# Keng_Seng_Task_2.net
KiCad netlist of a schematic drawn in Altium Designer
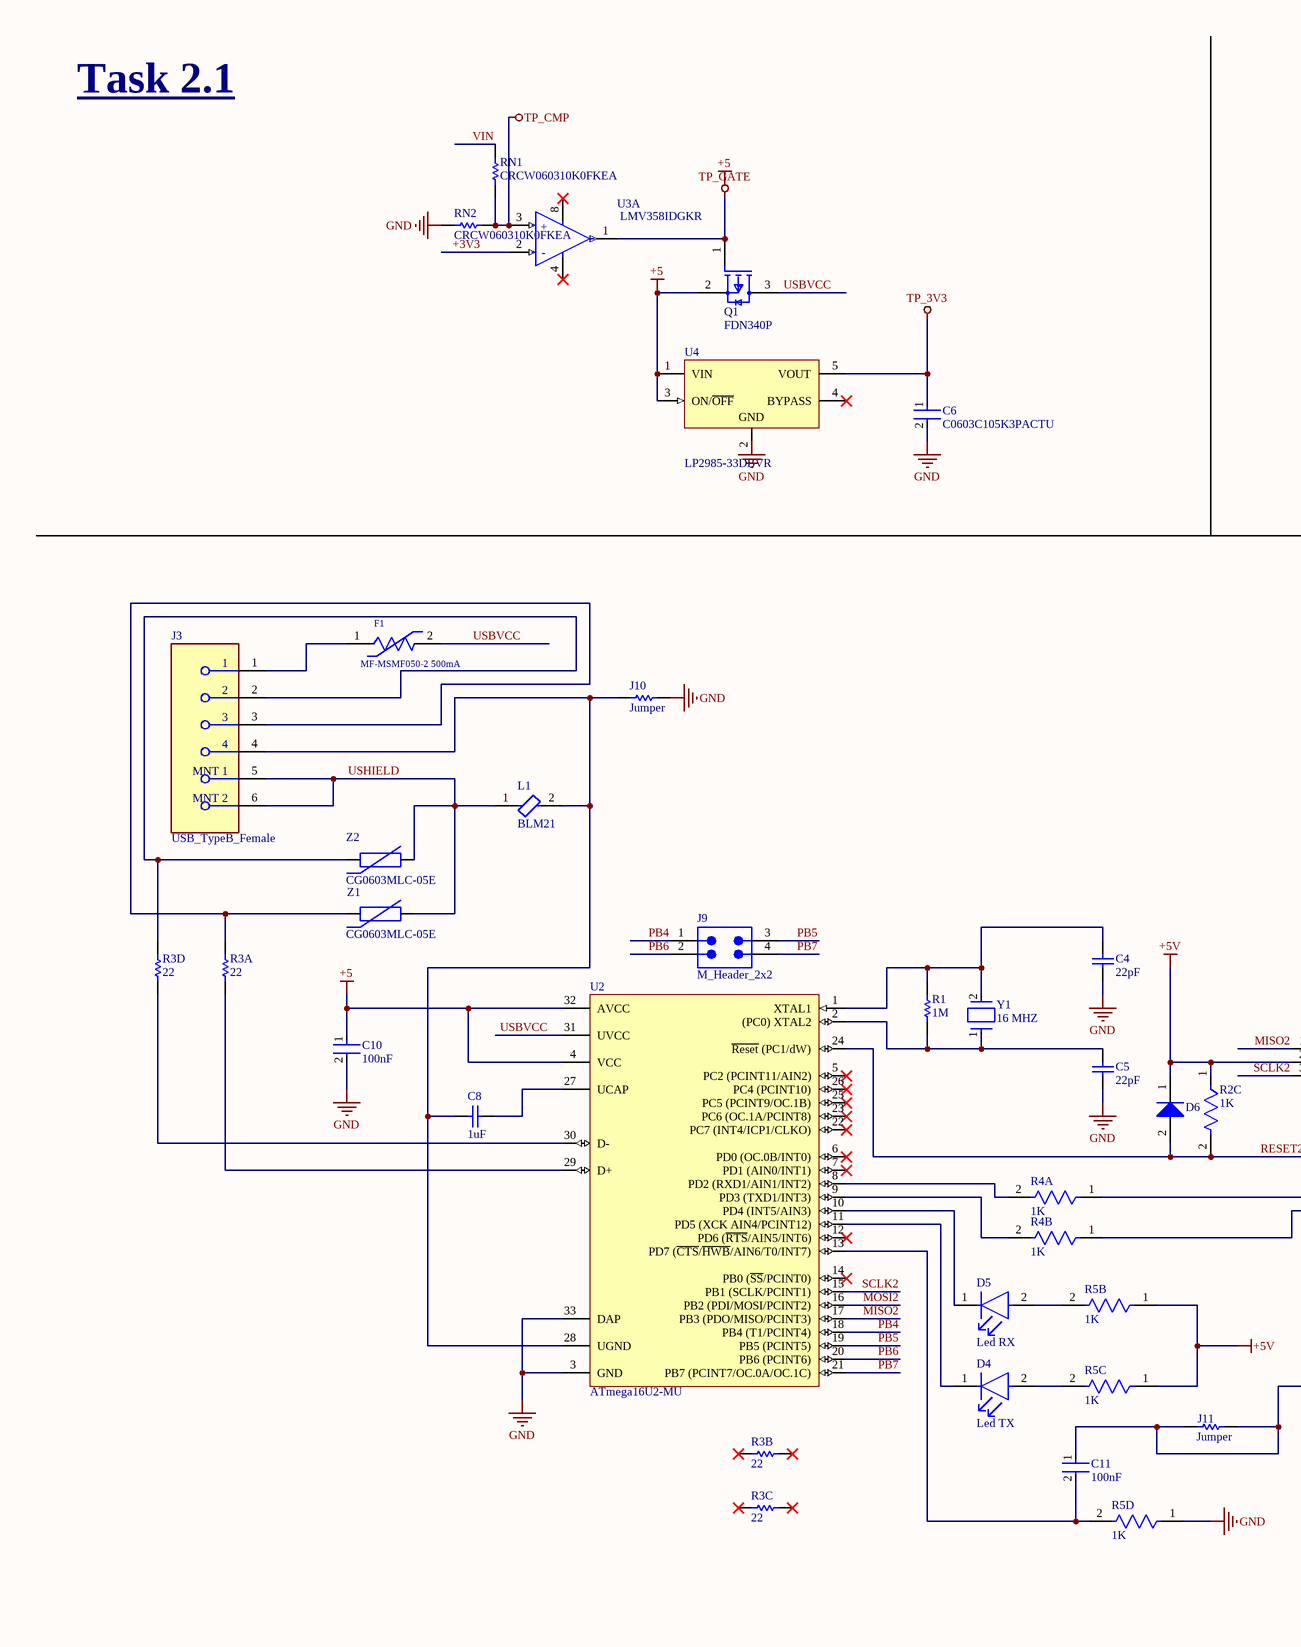
[diagram p0: Keng Seng Task 2.SchDoc, left]
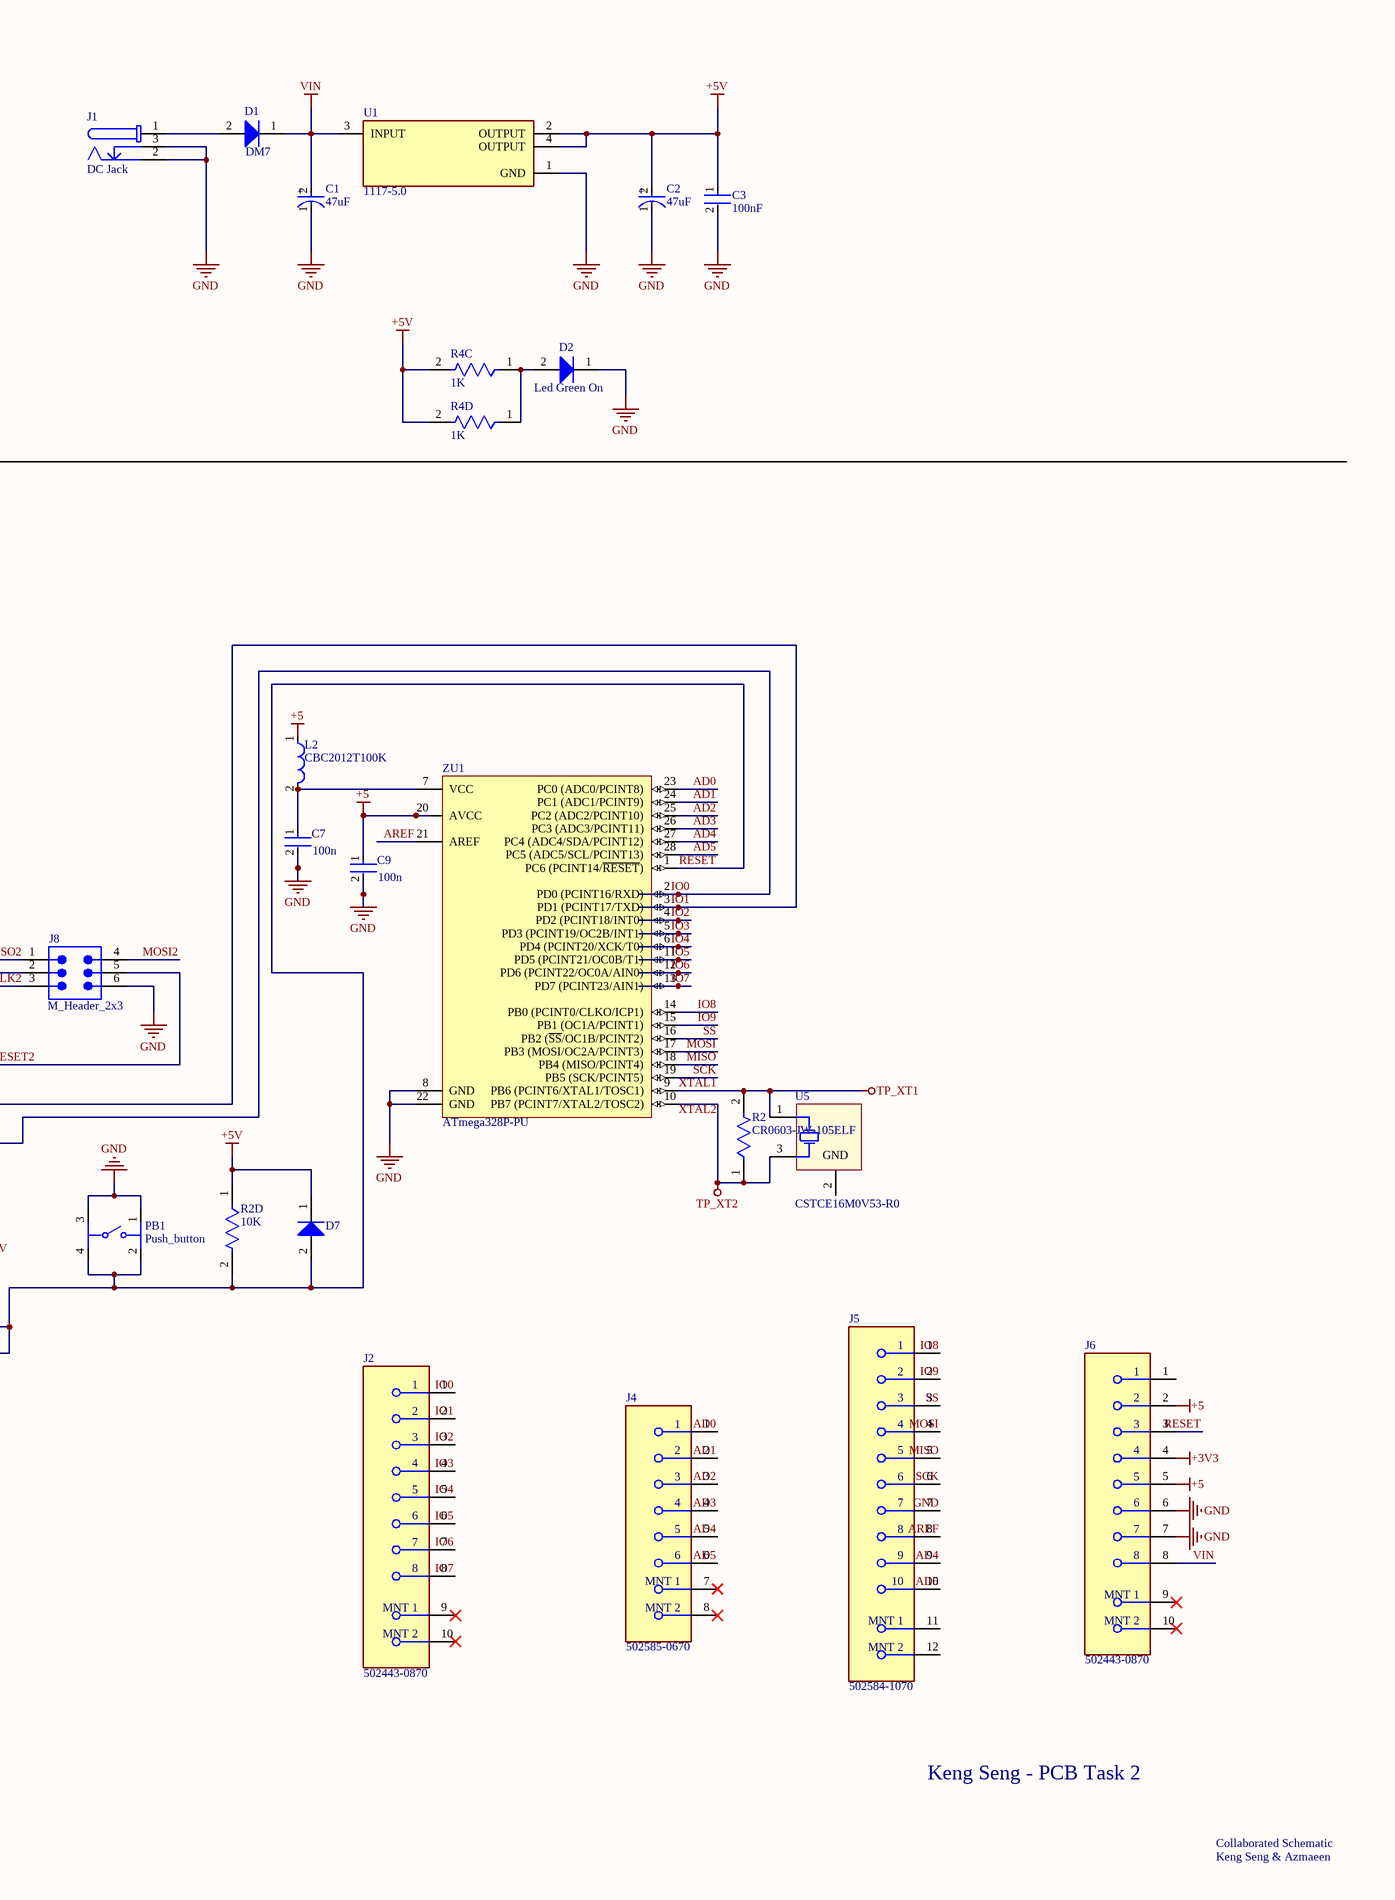
[diagram p1: Keng Seng Task 2.SchDoc, right]

(export (version "E")
  (design (tool "Eeschema 10.0.6"))
  (components
    (comp (ref "C1")
      (value "47uF")
      (footprint "FP-FPD-MFG")
      (description "CAP ALUM 47UF 20% 35V SMD")
      (fields (field (name "TOLERANCE") "20%") (field (name "VOLTAGE") "35V"))
      (libsource (lib "Altium Content Vault") (part "cf48714ba7e38822c1575c7ec0b6d1f"))
    )
    (comp (ref "C2")
      (value "47uF")
      (footprint "FP-FPD-MFG")
      (description "CAP ALUM 47UF 20% 35V SMD")
      (fields (field (name "TOLERANCE") "20%") (field (name "VOLTAGE") "35V"))
      (libsource (lib "Altium Content Vault") (part "cf48714ba7e38822c1575c7ec0b6d1f"))
    )
    (comp (ref "C3")
      (value "100nF")
      (footprint "FP-C0402-BB-MFG")
      (description "CAP CER 0.1UF 10V X5R 0402")
      (fields (field (name "MANUFACTURER") "Kemet") (field (name "TOLERANCE") "0.1"))
      (libsource (lib "Altium Content Vault") (part "b4654b650e69147ec39a6b967a45e02"))
    )
    (comp (ref "C4")
      (value "22pF")
      (footprint "CAPC1608X90X35ML10T15")
      (description "Chip Capacitor, 22 pF, +/- 5%, 50 V, -55 to 125 degC, 0603 (1608 Metric), RoHS, Tape and Reel")
      (fields (field (name "MANUFACTURER") "Murata"))
      (libsource (lib "Altium Content Vault") (part "CAP-NP-2"))
    )
    (comp (ref "C5")
      (value "22pF")
      (footprint "CAPC1608X90X35ML10T15")
      (description "Chip Capacitor, 22 pF, +/- 5%, 50 V, -55 to 125 degC, 0603 (1608 Metric), RoHS, Tape and Reel")
      (fields (field (name "MANUFACTURER") "Murata"))
      (libsource (lib "Altium Content Vault") (part "CAP-NP-2"))
    )
    (comp (ref "C6")
      (value "C0603C105K3PACTU")
      (footprint "FP-C0603C105K3PACTU-MFG")
      (description "CAP CER 1UF 25V X5R 0603")
      (fields (field (name "VOLTAGE") "25V") (field (name "TOLERANCE") "10%"))
      (libsource (lib "Altium Content Vault") (part "e9c51b7dd13d4faca003ae77663ab08"))
    )
    (comp (ref "C7")
      (value "100n")
      (footprint "FP-C0603-030-0_03-IPC_A")
      (description "Multilayer Ceramic Capacitors 100pF ±5% 50V C0G SMD 0201")
      (fields (field (name "TOLERANCE") "5%") (field (name "VOLTAGE") "50V"))
      (libsource (lib "Altium Content Vault") (part "02cd4be3c70576c341d710602a673aa"))
    )
    (comp (ref "C8")
      (value "1uF")
      (footprint "CAPC2013X135X45LL10T25")
      (fields (field (name "MANUFACTURER") "Murata") (field (name "PART NUMBER") "GRM21BR71H105KA12L"))
      (libsource (lib "Altium Content Vault") (part "CAP"))
    )
    (comp (ref "C9")
      (value "100n")
      (footprint "FP-C0603-030-0_03-IPC_A")
      (description "Multilayer Ceramic Capacitors 100pF ±5% 50V C0G SMD 0201")
      (fields (field (name "TOLERANCE") "5%") (field (name "VOLTAGE") "50V"))
      (libsource (lib "Altium Content Vault") (part "02cd4be3c70576c341d710602a673aa"))
    )
    (comp (ref "C10")
      (value "100nF")
      (footprint "FP-C0402-BB-MFG")
      (description "CAP CER 0.1UF 10V X5R 0402")
      (fields (field (name "MANUFACTURER") "Kemet") (field (name "TOLERANCE") "0.1"))
      (libsource (lib "Altium Content Vault") (part "b4654b650e69147ec39a6b967a45e02"))
    )
    (comp (ref "C11")
      (value "100nF")
      (footprint "FP-C0402-BB-MFG")
      (description "CAP CER 0.1UF 10V X5R 0402")
      (fields (field (name "MANUFACTURER") "Kemet") (field (name "TOLERANCE") "0.1"))
      (libsource (lib "Altium Content Vault") (part "b4654b650e69147ec39a6b967a45e02"))
    )
    (comp (ref "D1")
      (value "DM7")
      (footprint "ONSC-SOD-323-2-477-02_V")
      (description "Schottky Barrier Diode, 2-Pin SOD-323, Pb-Free, Tape and Reel")
      (fields (field (name "PARTNUMBER") "BAT54HT1G") (field (name "MANUFACTURER") "On Semiconductor"))
      (libsource (lib "Altium Content Vault") (part "ONSC-D-K1A2-2"))
    )
    (comp (ref "D2")
      (value "Led Green On")
      (footprint "ONSC-SOD-323-2-477-02_V")
      (description "Schottky Barrier Diode, 2-Pin SOD-323, Pb-Free, Tape and Reel")
      (fields (field (name "PARTNUMBER") "BAT54HT1G") (field (name "MANUFACTURER") "On Semiconductor"))
      (libsource (lib "Altium Content Vault") (part "ONSC-D-K1A2-2"))
    )
    (comp (ref "D4")
      (value "Led TX")
      (footprint "FP-LTST-C190GKT-MFG")
      (description "LED GREEN CLEAR CHIP SMD")
      (fields (field (name "VOLTAGE") "2V"))
      (libsource (lib "Altium Content Vault") (part "8706943c75ba83719d021d2fdc84c58"))
    )
    (comp (ref "D5")
      (value "Led RX")
      (footprint "FP-LTST-C190GKT-MFG")
      (description "LED GREEN CLEAR CHIP SMD")
      (fields (field (name "VOLTAGE") "2V"))
      (libsource (lib "Altium Content Vault") (part "8706943c75ba83719d021d2fdc84c58"))
    )
    (comp (ref "D6")
      (value "~")
      (footprint "ONSC-SOD-323-2-477-02_V")
      (description "Schottky Barrier Diode, 2-Pin SOD-323, Pb-Free, Tape and Reel")
      (fields (field (name "PARTNUMBER") "BAT54HT1G") (field (name "MANUFACTURER") "On Semiconductor"))
      (libsource (lib "Altium Content Vault") (part "ONSC-D-K1A2-2"))
    )
    (comp (ref "D7")
      (value "~")
      (footprint "ONSC-SOD-323-2-477-02_V")
      (description "Schottky Barrier Diode, 2-Pin SOD-323, Pb-Free, Tape and Reel")
      (fields (field (name "PARTNUMBER") "BAT54HT1G") (field (name "MANUFACTURER") "On Semiconductor"))
      (libsource (lib "Altium Content Vault") (part "ONSC-D-K1A2-2"))
    )
    (comp (ref "F1")
      (value "MF-MSMF050-2 500mA")
      (footprint "FP-MF-MSMF050-2-MFG")
      (description "PTC RESET FUSE 15V 500MA 1812")
      (fields (field (name "MANUFACTURER") "Bourns") (field (name "MANUFACTURER PART NUMBER") "MF-MSMF050-2"))
      (libsource (lib "Altium Content Vault") (part "fc31388045fc42ab786d6d00b506e9f"))
    )
    (comp (ref "J1")
      (value "DC Jack")
      (footprint "694105309102")
      (libsource (lib "Altium Content Vault") (part "DC Power Jack"))
    )
    (comp (ref "J2")
      (value "502443-0870")
      (footprint "FP-502443-0870-MFG")
      (description "502443-0870 2.00mm Pitch CLIK-Mate Wire-to-Board PCB Receptacle, Single Row, Vertical, 8 Circuits")
      (libsource (lib "Altium Content Vault") (part "cba65c9947a6637759d8dec63cb3c15"))
    )
    (comp (ref "J3")
      (value "USB_TypeB_Female")
      (footprint "FP-1-1734346-1-MFG")
      (description "CONN RCPT USB2.0 TYPEB 4P SMD RA")
      (fields (field (name "MANUFACTURER") "TE") (field (name "MANUFACTURER PART NUMBER") "1-1734346-1"))
      (libsource (lib "Altium Content Vault") (part "3cf8230c7ca2247c71501eddf00a6f6"))
    )
    (comp (ref "J4")
      (value "502585-0670")
      (footprint "FP-502585-0670-MFG")
      (description "CONN RCPT 6POS 0.059 TIN SMD R/A")
      (libsource (lib "Altium Content Vault") (part "8c94e21e9c131abf164ed80b5483a23"))
    )
    (comp (ref "J5")
      (value "502584-1070")
      (footprint "FP-502584-1070-MFG")
      (description "502584-1070 1.5 W/B Sgl ST RecAssy10CktEmbsTpPkg")
      (libsource (lib "Altium Content Vault") (part "1c0ca442a5954ba4a967f3d0734fb97"))
    )
    (comp (ref "J6")
      (value "502443-0870")
      (footprint "FP-502443-0870-MFG")
      (description "502443-0870 2.00mm Pitch CLIK-Mate Wire-to-Board PCB Receptacle, Single Row, Vertical, 8 Circuits")
      (libsource (lib "Altium Content Vault") (part "cba65c9947a6637759d8dec63cb3c15"))
    )
    (comp (ref "J8")
      (value "M_Header_2x3")
      (footprint "66200621022")
      (libsource (lib "Altium Content Vault") (part "Header_Male_2R_06P(A)"))
    )
    (comp (ref "J9")
      (value "M_Header_2x2")
      (footprint "66200421022")
      (libsource (lib "Altium Content Vault") (part "Header_Male_2R_04P(A)"))
    )
    (comp (ref "J10")
      (value "Jumper")
      (footprint "RESC2013X50X30LL20T20")
      (fields (field (name "MANUFACTURER") "Vishay Dale") (field (name "PART NUMBER") "CRCW08050000Z0EA"))
      (libsource (lib "Altium Content Vault") (part "RES"))
    )
    (comp (ref "J11")
      (value "Jumper")
      (footprint "RESC2013X50X30LL20T20")
      (fields (field (name "MANUFACTURER") "Vishay Dale") (field (name "PART NUMBER") "CRCW08050000Z0EA"))
      (libsource (lib "Altium Content Vault") (part "RES"))
    )
    (comp (ref "L1")
      (value "BLM21")
      (footprint "FP-BLM21-0_2-t0_85-e0_5-MFG")
      (description "Chip Ferrite Bead, 0805, 600Ω @ 100MHz, 0.2Ω, 25%, 700mA")
      (fields (field (name "TOLERANCE") "25%"))
      (libsource (lib "Altium Content Vault") (part "5f30dd21d616792df468990f7003faa"))
    )
    (comp (ref "L2")
      (value "CBC2012T100K")
      (footprint "FP-CB2012-IPC_A")
      (description "SMD Inductors 10uH ±10% 0.34A 1.56Ω 0805")
      (fields (field (name "TOLERANCE") "10%"))
      (libsource (lib "Altium Content Vault") (part "725321dda6339637d4d059423bc1c3c"))
    )
    (comp (ref "PB1")
      (value "Push_button")
      (footprint "FP-PTS645SM43SMTR92LFS-MFG")
      (description "SWITCH TACTILE SPST-NO 0.05A 12V")
      (libsource (lib "Altium Content Vault") (part "1adf0dd01260c80cf25a44bfd6b99ba"))
    )
    (comp (ref "Q1")
      (value "FDN340P")
      (footprint "FP-527AG-MFG")
      (description "MOSFET P-CH 20V 2A SSOT3")
      (libsource (lib "Altium Content Vault") (part "d23f43cc42f60b967b7caccf14518fd"))
    )
    (comp (ref "R1")
      (value "1M")
      (footprint "RESC3216X70X50NL05T20")
      (fields (field (name "MANUFACTURER") "Panasonic") (field (name "PART NUMBER") "ERJ-8GEY0R00V"))
      (libsource (lib "Altium Content Vault") (part "RES"))
    )
    (comp (ref "R2")
      (value "CR0603-JW-105ELF")
      (footprint "FP-CR0603-IPC_A")
      (description "Thick Film Chip Resistors 0603 1MΩ 0.1W 5% 200ppm/°C")
      (fields (field (name "TOLERANCE") "5%"))
      (libsource (lib "Altium Content Vault") (part "1029c3af85768c4190bb7ad29bc67b5"))
    )
    (comp (ref "R2C")
      (value "1K")
      (footprint "FP-CRCW0603-e3-MFG")
      (description "RES Thick Film, 1kΩ, 1%, 0.1W, 100ppm/°C, 0603")
      (fields (field (name "TOLERANCE") "1%"))
      (libsource (lib "Altium Content Vault") (part "1029c3af85768c4190bb7ad29bc67b5"))
    )
    (comp (ref "R2D")
      (value "10K")
      (footprint "FP-CRCW0603-e3-MFG")
      (description "RES Thick Film, 1kΩ, 1%, 0.1W, 100ppm/°C, 0603")
      (fields (field (name "TOLERANCE") "1%"))
      (libsource (lib "Altium Content Vault") (part "1029c3af85768c4190bb7ad29bc67b5"))
    )
    (comp (ref "R3A")
      (value "22")
      (footprint "RESC1005X40X25LL05T05")
      (fields (field (name "MANUFACTURER") "Vishay Dale") (field (name "PART NUMBER") "CRCW040222R0FKED"))
      (libsource (lib "Altium Content Vault") (part "RES"))
    )
    (comp (ref "R3B")
      (value "22")
      (footprint "RESC1005X40X25LL05T05")
      (fields (field (name "MANUFACTURER") "Vishay Dale") (field (name "PART NUMBER") "CRCW040222R0FKED"))
      (libsource (lib "Altium Content Vault") (part "RES"))
    )
    (comp (ref "R3C")
      (value "22")
      (footprint "RESC1005X40X25LL05T05")
      (fields (field (name "MANUFACTURER") "Vishay Dale") (field (name "PART NUMBER") "CRCW040222R0FKED"))
      (libsource (lib "Altium Content Vault") (part "RES"))
    )
    (comp (ref "R3D")
      (value "22")
      (footprint "RESC1005X40X25LL05T05")
      (fields (field (name "MANUFACTURER") "Vishay Dale") (field (name "PART NUMBER") "CRCW040222R0FKED"))
      (libsource (lib "Altium Content Vault") (part "RES"))
    )
    (comp (ref "R4A")
      (value "1K")
      (footprint "FP-CRCW0603-e3-MFG")
      (description "RES Thick Film, 1kΩ, 1%, 0.1W, 100ppm/°C, 0603")
      (fields (field (name "TOLERANCE") "1%"))
      (libsource (lib "Altium Content Vault") (part "1029c3af85768c4190bb7ad29bc67b5"))
    )
    (comp (ref "R4B")
      (value "1K")
      (footprint "FP-CRCW0603-e3-MFG")
      (description "RES Thick Film, 1kΩ, 1%, 0.1W, 100ppm/°C, 0603")
      (fields (field (name "TOLERANCE") "1%"))
      (libsource (lib "Altium Content Vault") (part "1029c3af85768c4190bb7ad29bc67b5"))
    )
    (comp (ref "R4C")
      (value "1K")
      (footprint "FP-CRCW0603-e3-MFG")
      (description "RES Thick Film, 1kΩ, 1%, 0.1W, 100ppm/°C, 0603")
      (fields (field (name "TOLERANCE") "1%"))
      (libsource (lib "Altium Content Vault") (part "1029c3af85768c4190bb7ad29bc67b5"))
    )
    (comp (ref "R4D")
      (value "1K")
      (footprint "FP-CRCW0603-e3-MFG")
      (description "RES Thick Film, 1kΩ, 1%, 0.1W, 100ppm/°C, 0603")
      (fields (field (name "TOLERANCE") "1%"))
      (libsource (lib "Altium Content Vault") (part "1029c3af85768c4190bb7ad29bc67b5"))
    )
    (comp (ref "R5B")
      (value "1K")
      (footprint "FP-CRCW0603-e3-MFG")
      (description "RES Thick Film, 1kΩ, 1%, 0.1W, 100ppm/°C, 0603")
      (fields (field (name "TOLERANCE") "1%"))
      (libsource (lib "Altium Content Vault") (part "1029c3af85768c4190bb7ad29bc67b5"))
    )
    (comp (ref "R5C")
      (value "1K")
      (footprint "FP-CRCW0603-e3-MFG")
      (description "RES Thick Film, 1kΩ, 1%, 0.1W, 100ppm/°C, 0603")
      (fields (field (name "TOLERANCE") "1%"))
      (libsource (lib "Altium Content Vault") (part "1029c3af85768c4190bb7ad29bc67b5"))
    )
    (comp (ref "R5D")
      (value "1K")
      (footprint "FP-CRCW0603-e3-MFG")
      (description "RES Thick Film, 1kΩ, 1%, 0.1W, 100ppm/°C, 0603")
      (fields (field (name "TOLERANCE") "1%"))
      (libsource (lib "Altium Content Vault") (part "1029c3af85768c4190bb7ad29bc67b5"))
    )
    (comp (ref "RN1")
      (value "CRCW060310K0FKEA")
      (footprint "RESC1609X50X30NL8T20")
      (description "Chip Resistor, 10 KOhm, +/- 1%, 100 mW, -55 to 155 degC, 0603 (1608 Metric), RoHS, Tape and Reel")
      (fields (field (name "MANUFACTURER") "Vishay Semiconductor"))
      (libsource (lib "Altium Content Vault") (part "RES-2"))
    )
    (comp (ref "RN2")
      (value "CRCW060310K0FKEA")
      (footprint "RESC1609X50X30NL8T20")
      (description "Chip Resistor, 10 KOhm, +/- 1%, 100 mW, -55 to 155 degC, 0603 (1608 Metric), RoHS, Tape and Reel")
      (fields (field (name "MANUFACTURER") "Vishay Semiconductor"))
      (libsource (lib "Altium Content Vault") (part "RES-2"))
    )
    (comp (ref "U1")
      (value "1117-5.0")
      (footprint "FP-DCY0004A-IPC_A")
      (description "IC REG LINEAR 5V 800MA SOT223-4")
      (libsource (lib "Altium Content Vault") (part "e308c0431133a401381f8e374ae96fd"))
    )
    (comp (ref "U2")
      (value "ATmega16U2-MU")
      (footprint "32PG_N")
      (libsource (lib "Altium Content Vault") (part "MC-8B-ATM8U2-SQ33"))
    )
    (comp (ref "U3")
      (value "LMV358IDGKR")
      (footprint "FP-DGK0008A-IPC_B")
      (description "IC OPAMP GP 2 CIRCUIT 8VSSOP")
      (libsource (lib "Altium Content Vault") (part "0c8284b4894d20c9a71d669de4a4eff"))
    )
    (comp (ref "U4")
      (value "LP2985-33DBVR")
      (footprint "DBV0005A_M")
      (fields (field (name "MANUFACTURER") "Texas Instruments"))
      (libsource (lib "Altium Content Vault") (part "TI-LP2985_A-10DBV5"))
    )
    (comp (ref "U5")
      (value "CSTCE16M0V53-R0")
      (footprint "MURA-CSTCE_V-3_V")
      (fields (field (name "MANUFACTURER") "Murata"))
      (libsource (lib "Altium Content Vault") (part "MURA-CSTCE_V-3"))
    )
    (comp (ref "Y1")
      (value "16 MHZ")
      (footprint "FP-ABM7-MFG")
      (description "Crystal 16MHz ±20ppm 18pF SMD-2 6mm x 3.5mm")
      (fields (field (name "TOLERANCE") "20ppm"))
      (libsource (lib "Altium Content Vault") (part "c23a69dc6c9e2f18f2079038eb95dd1"))
    )
    (comp (ref "Z1")
      (value "CG0603MLC-05E")
      (footprint "BOUR-CG0603-2_V")
      (description "ESD Protector, 5 V Supply, -40 to 85 degC, 1.6 x 0.8 x 0.55 mm SMD, RoHS, Tape and Reel")
      (fields (field (name "MANUFACTURER") "Bourns"))
      (libsource (lib "Altium Content Vault") (part "BOUR-VSR-2"))
    )
    (comp (ref "Z2")
      (value "CG0603MLC-05E")
      (footprint "BOUR-CG0603-2_V")
      (description "ESD Protector, 5 V Supply, -40 to 85 degC, 1.6 x 0.8 x 0.55 mm SMD, RoHS, Tape and Reel")
      (fields (field (name "MANUFACTURER") "Bourns"))
      (libsource (lib "Altium Content Vault") (part "BOUR-VSR-2"))
    )
    (comp (ref "ZU1")
      (value "ATmega328P-PU")
      (footprint "28P3")
      (libsource (lib "Altium Content Vault") (part "MC-8B-ATM48-IL28"))
    )
  )
  (nets
    (net (code "1") (name "+3V3") (class "Default")
      (node (ref "J6") (pin "4") (pinfunction "4_4") (pintype "passive"))
      (node (ref "U3") (pin "2") (pinfunction "1IN-_2") (pintype "input"))
    )
    (net (code "2") (name "+5") (class "Default")
      (node (ref "C10") (pin "1") (pinfunction "1_1") (pintype "passive"))
      (node (ref "C9") (pin "1") (pinfunction "1_1") (pintype "passive"))
      (node (ref "J6") (pin "2") (pinfunction "2_2") (pintype "passive"))
      (node (ref "J6") (pin "5") (pinfunction "5_5") (pintype "passive"))
      (node (ref "L2") (pin "1") (pinfunction "1_1") (pintype "passive"))
      (node (ref "Q1") (pin "2") (pinfunction "S_2") (pintype "passive"))
      (node (ref "U2") (pin "32") (pinfunction "AVCC_32") (pintype "power_in"))
      (node (ref "U2") (pin "4") (pinfunction "VCC_4") (pintype "power_in"))
      (node (ref "U4") (pin "1") (pinfunction "VIN_1") (pintype "power_in"))
      (node (ref "U4") (pin "3") (pinfunction "ON/~{OFF}_3") (pintype "input"))
      (node (ref "ZU1") (pin "20") (pinfunction "AVCC_20") (pintype "power_in"))
    )
    (net (code "3") (name "+5V") (class "Default")
      (node (ref "C2") (pin "2") (pinfunction "A_2") (pintype "passive"))
      (node (ref "C3") (pin "1") (pinfunction "1_1") (pintype "passive"))
      (node (ref "D6") (pin "1") (pinfunction "K_1") (pintype "passive"))
      (node (ref "D7") (pin "1") (pinfunction "K_1") (pintype "passive"))
      (node (ref "J8") (pin "2") (pinfunction "2_2") (pintype "passive"))
      (node (ref "R2C") (pin "1") (pinfunction "1_1") (pintype "passive"))
      (node (ref "R2D") (pin "1") (pinfunction "1_1") (pintype "passive"))
      (node (ref "R4C") (pin "2") (pinfunction "2_2") (pintype "passive"))
      (node (ref "R4D") (pin "2") (pinfunction "2_2") (pintype "passive"))
      (node (ref "R5B") (pin "1") (pinfunction "1_1") (pintype "passive"))
      (node (ref "R5C") (pin "1") (pinfunction "1_1") (pintype "passive"))
      (node (ref "U1") (pin "2") (pinfunction "OUTPUT_2") (pintype "power_in"))
      (node (ref "U1") (pin "4") (pinfunction "OUTPUT_4") (pintype "power_in"))
    )
    (net (code "4") (name "/AD0") (class "Default")
      (node (ref "J4") (pin "1") (pinfunction "1_1") (pintype "passive"))
      (node (ref "ZU1") (pin "23") (pinfunction "PC0_(ADC0/PCINT8)_23") (pintype "bidirectional"))
    )
    (net (code "5") (name "/AD1") (class "Default")
      (node (ref "J4") (pin "2") (pinfunction "2_2") (pintype "passive"))
      (node (ref "ZU1") (pin "24") (pinfunction "PC1_(ADC1/PCINT9)_24") (pintype "bidirectional"))
    )
    (net (code "6") (name "/AD2") (class "Default")
      (node (ref "J4") (pin "3") (pinfunction "3_3") (pintype "passive"))
      (node (ref "ZU1") (pin "25") (pinfunction "PC2_(ADC2/PCINT10)_25") (pintype "bidirectional"))
    )
    (net (code "7") (name "/AD3") (class "Default")
      (node (ref "J4") (pin "4") (pinfunction "4_4") (pintype "passive"))
      (node (ref "ZU1") (pin "26") (pinfunction "PC3_(ADC3/PCINT11)_26") (pintype "bidirectional"))
    )
    (net (code "8") (name "/AD4") (class "Default")
      (node (ref "J4") (pin "5") (pinfunction "5_5") (pintype "passive"))
      (node (ref "J5") (pin "9") (pinfunction "9_9") (pintype "passive"))
      (node (ref "ZU1") (pin "27") (pinfunction "PC4_(ADC4/SDA/PCINT12)_27") (pintype "bidirectional"))
    )
    (net (code "9") (name "/AD5") (class "Default")
      (node (ref "J4") (pin "6") (pinfunction "6_6") (pintype "passive"))
      (node (ref "J5") (pin "10") (pinfunction "10_10") (pintype "passive"))
      (node (ref "ZU1") (pin "28") (pinfunction "PC5_(ADC5/SCL/PCINT13)_28") (pintype "bidirectional"))
    )
    (net (code "10") (name "/AREF") (class "Default")
      (node (ref "J5") (pin "8") (pinfunction "8_8") (pintype "passive"))
      (node (ref "ZU1") (pin "21") (pinfunction "AREF_21") (pintype "power_in"))
    )
    (net (code "11") (name "/IO0") (class "Default")
      (node (ref "J2") (pin "1") (pinfunction "1_1") (pintype "passive"))
      (node (ref "R4B") (pin "1") (pinfunction "1_1") (pintype "passive"))
      (node (ref "ZU1") (pin "2") (pinfunction "PD0_(PCINT16/RXD)_2") (pintype "bidirectional"))
    )
    (net (code "12") (name "/IO1") (class "Default")
      (node (ref "J2") (pin "2") (pinfunction "2_2") (pintype "passive"))
      (node (ref "R4A") (pin "1") (pinfunction "1_1") (pintype "passive"))
      (node (ref "ZU1") (pin "3") (pinfunction "PD1_(PCINT17/TXD)_3") (pintype "bidirectional"))
    )
    (net (code "13") (name "/IO2") (class "Default")
      (node (ref "J2") (pin "3") (pinfunction "3_3") (pintype "passive"))
      (node (ref "ZU1") (pin "4") (pinfunction "PD2_(PCINT18/INT0)_4") (pintype "bidirectional"))
    )
    (net (code "14") (name "/IO3") (class "Default")
      (node (ref "J2") (pin "4") (pinfunction "4_4") (pintype "passive"))
      (node (ref "ZU1") (pin "5") (pinfunction "PD3_(PCINT19/OC2B/INT1)_5") (pintype "bidirectional"))
    )
    (net (code "15") (name "/IO4") (class "Default")
      (node (ref "J2") (pin "5") (pinfunction "5_5") (pintype "passive"))
      (node (ref "ZU1") (pin "6") (pinfunction "PD4_(PCINT20/XCK/T0)_6") (pintype "bidirectional"))
    )
    (net (code "16") (name "/IO5") (class "Default")
      (node (ref "J2") (pin "6") (pinfunction "6_6") (pintype "passive"))
      (node (ref "ZU1") (pin "11") (pinfunction "PD5_(PCINT21/OC0B/T1)_11") (pintype "bidirectional"))
    )
    (net (code "17") (name "/IO6") (class "Default")
      (node (ref "J2") (pin "7") (pinfunction "7_7") (pintype "passive"))
      (node (ref "ZU1") (pin "12") (pinfunction "PD6_(PCINT22/OC0A/AIN0)_12") (pintype "bidirectional"))
    )
    (net (code "18") (name "/IO7") (class "Default")
      (node (ref "J2") (pin "8") (pinfunction "8_8") (pintype "passive"))
      (node (ref "ZU1") (pin "13") (pinfunction "PD7_(PCINT23/AIN1)_13") (pintype "bidirectional"))
    )
    (net (code "19") (name "/IO8") (class "Default")
      (node (ref "J5") (pin "1") (pinfunction "1_1") (pintype "passive"))
      (node (ref "ZU1") (pin "14") (pinfunction "PB0_(PCINT0/CLKO/ICP1)_14") (pintype "bidirectional"))
    )
    (net (code "20") (name "/IO9") (class "Default")
      (node (ref "J5") (pin "2") (pinfunction "2_2") (pintype "passive"))
      (node (ref "ZU1") (pin "15") (pinfunction "PB1_(OC1A/PCINT1)_15") (pintype "bidirectional"))
    )
    (net (code "21") (name "/MISO") (class "Default")
      (node (ref "J5") (pin "5") (pinfunction "5_5") (pintype "passive"))
      (node (ref "ZU1") (pin "18") (pinfunction "PB4_(MISO/PCINT4)_18") (pintype "bidirectional"))
    )
    (net (code "22") (name "/MISO2") (class "Default")
      (node (ref "J8") (pin "1") (pinfunction "1_1") (pintype "passive"))
      (node (ref "U2") (pin "17") (pinfunction "PB3_(PDO/MISO/PCINT3)_17") (pintype "bidirectional"))
    )
    (net (code "23") (name "/MOSI") (class "Default")
      (node (ref "J5") (pin "4") (pinfunction "4_4") (pintype "passive"))
      (node (ref "ZU1") (pin "17") (pinfunction "PB3_(MOSI/OC2A/PCINT3)_17") (pintype "bidirectional"))
    )
    (net (code "24") (name "/MOSI2") (class "Default")
      (node (ref "J8") (pin "4") (pinfunction "4_4") (pintype "passive"))
      (node (ref "U2") (pin "16") (pinfunction "PB2_(PDI/MOSI/PCINT2)_16") (pintype "bidirectional"))
    )
    (net (code "25") (name "/PB4") (class "Default")
      (node (ref "J9") (pin "1") (pinfunction "1_1") (pintype "passive"))
      (node (ref "U2") (pin "18") (pinfunction "PB4_(T1/PCINT4)_18") (pintype "bidirectional"))
    )
    (net (code "26") (name "/PB5") (class "Default")
      (node (ref "J9") (pin "3") (pinfunction "3_3") (pintype "passive"))
      (node (ref "U2") (pin "19") (pinfunction "PB5_(PCINT5)_19") (pintype "bidirectional"))
    )
    (net (code "27") (name "/PB6") (class "Default")
      (node (ref "J9") (pin "2") (pinfunction "2_2") (pintype "passive"))
      (node (ref "U2") (pin "20") (pinfunction "PB6_(PCINT6)_20") (pintype "bidirectional"))
    )
    (net (code "28") (name "/PB7") (class "Default")
      (node (ref "J9") (pin "4") (pinfunction "4_4") (pintype "passive"))
      (node (ref "U2") (pin "21") (pinfunction "PB7_(PCINT7/OC.0A/OC.1C)_21") (pintype "bidirectional"))
    )
    (net (code "29") (name "/RESET") (class "Default")
      (node (ref "C11") (pin "1") (pinfunction "1_1") (pintype "passive"))
      (node (ref "D7") (pin "2") (pinfunction "A_2") (pintype "passive"))
      (node (ref "J11") (pin "1") (pinfunction "1_1") (pintype "passive"))
      (node (ref "J11") (pin "2") (pinfunction "2_2") (pintype "passive"))
      (node (ref "J6") (pin "3") (pinfunction "3_3") (pintype "passive"))
      (node (ref "PB1") (pin "2") (pinfunction "2_2") (pintype "passive"))
      (node (ref "PB1") (pin "4") (pinfunction "4_4") (pintype "passive"))
      (node (ref "R2D") (pin "2") (pinfunction "2_2") (pintype "passive"))
      (node (ref "ZU1") (pin "1") (pinfunction "PC6_(PCINT14/~{RESET})_1") (pintype "bidirectional"))
    )
    (net (code "30") (name "/RESET2") (class "Default")
      (node (ref "D6") (pin "2") (pinfunction "A_2") (pintype "passive"))
      (node (ref "J8") (pin "5") (pinfunction "5_5") (pintype "passive"))
      (node (ref "R2C") (pin "2") (pinfunction "2_2") (pintype "passive"))
      (node (ref "U2") (pin "24") (pinfunction "~{Reset}_(PC1/dW)_24") (pintype "bidirectional"))
    )
    (net (code "31") (name "/SCK") (class "Default")
      (node (ref "J5") (pin "6") (pinfunction "6_6") (pintype "passive"))
      (node (ref "ZU1") (pin "19") (pinfunction "PB5_(SCK/PCINT5)_19") (pintype "bidirectional"))
    )
    (net (code "32") (name "/SCLK2") (class "Default")
      (node (ref "J8") (pin "3") (pinfunction "3_3") (pintype "passive"))
      (node (ref "U2") (pin "15") (pinfunction "PB1_(SCLK/PCINT1)_15") (pintype "bidirectional"))
    )
    (net (code "33") (name "/SS") (class "Default")
      (node (ref "J5") (pin "3") (pinfunction "3_3") (pintype "passive"))
      (node (ref "ZU1") (pin "16") (pinfunction "PB2_(~{SS}/OC1B/PCINT2)_16") (pintype "bidirectional"))
    )
    (net (code "34") (name "/USBVCC") (class "Default")
      (node (ref "F1") (pin "2") (pinfunction "2_2") (pintype "passive"))
      (node (ref "Q1") (pin "3") (pinfunction "D_3") (pintype "passive"))
      (node (ref "U2") (pin "31") (pinfunction "UVCC_31") (pintype "power_in"))
    )
    (net (code "35") (name "/USHIELD") (class "Default")
      (node (ref "J3") (pin "5") (pinfunction "MNT_1_5") (pintype "passive"))
      (node (ref "J3") (pin "6") (pinfunction "MNT_2_6") (pintype "passive"))
      (node (ref "L1") (pin "1") (pinfunction "1_1") (pintype "passive"))
      (node (ref "Z1") (pin "2") (pinfunction "2_2") (pintype "passive"))
      (node (ref "Z2") (pin "2") (pinfunction "2_2") (pintype "passive"))
    )
    (net (code "36") (name "GND") (class "Default")
      (node (ref "C1") (pin "1") (pinfunction "C_1") (pintype "passive"))
      (node (ref "C10") (pin "2") (pinfunction "2_2") (pintype "passive"))
      (node (ref "C2") (pin "1") (pinfunction "C_1") (pintype "passive"))
      (node (ref "C3") (pin "2") (pinfunction "2_2") (pintype "passive"))
      (node (ref "C4") (pin "1") (pinfunction "1_1") (pintype "passive"))
      (node (ref "C5") (pin "1") (pinfunction "1_1") (pintype "passive"))
      (node (ref "C6") (pin "2") (pinfunction "2_2") (pintype "passive"))
      (node (ref "C7") (pin "2") (pinfunction "2_2") (pintype "passive"))
      (node (ref "C9") (pin "2") (pinfunction "2_2") (pintype "passive"))
      (node (ref "D2") (pin "1") (pinfunction "K_1") (pintype "passive"))
      (node (ref "J1") (pin "2") (pinfunction "2_2") (pintype "passive"))
      (node (ref "J1") (pin "3") (pinfunction "3_3") (pintype "passive"))
      (node (ref "J10") (pin "1") (pinfunction "1_1") (pintype "passive"))
      (node (ref "J5") (pin "7") (pinfunction "7_7") (pintype "passive"))
      (node (ref "J6") (pin "6") (pinfunction "6_6") (pintype "passive"))
      (node (ref "J6") (pin "7") (pinfunction "7_7") (pintype "passive"))
      (node (ref "J8") (pin "6") (pinfunction "6_6") (pintype "passive"))
      (node (ref "PB1") (pin "1") (pinfunction "1_1") (pintype "passive"))
      (node (ref "PB1") (pin "3") (pinfunction "3_3") (pintype "passive"))
      (node (ref "R5D") (pin "1") (pinfunction "1_1") (pintype "passive"))
      (node (ref "RN2") (pin "1") (pinfunction "1_1") (pintype "passive"))
      (node (ref "U1") (pin "1") (pinfunction "GND_1") (pintype "power_in"))
      (node (ref "U2") (pin "3") (pinfunction "GND_3") (pintype "power_in"))
      (node (ref "U2") (pin "33") (pinfunction "DAP_33") (pintype "power_in"))
      (node (ref "ZU1") (pin "22") (pinfunction "GND_22") (pintype "power_in"))
      (node (ref "ZU1") (pin "8") (pinfunction "GND_8") (pintype "power_in"))
    )
    (net (code "37") (name "Net-(D1-A)") (class "Default")
      (node (ref "D1") (pin "2") (pinfunction "A_2") (pintype "passive"))
      (node (ref "J1") (pin "1") (pinfunction "1_1") (pintype "passive"))
    )
    (net (code "38") (name "Net-(D2-A)") (class "Default")
      (node (ref "D2") (pin "2") (pinfunction "A_2") (pintype "passive"))
      (node (ref "R4C") (pin "1") (pinfunction "1_1") (pintype "passive"))
      (node (ref "R4D") (pin "1") (pinfunction "1_1") (pintype "passive"))
    )
    (net (code "39") (name "Net-(D4-A)") (class "Default")
      (node (ref "D4") (pin "2") (pinfunction "A_2") (pintype "passive"))
      (node (ref "R5C") (pin "2") (pinfunction "2_2") (pintype "passive"))
    )
    (net (code "40") (name "Net-(D4-C)") (class "Default")
      (node (ref "D4") (pin "1") (pinfunction "C_1") (pintype "passive"))
      (node (ref "U2") (pin "11") (pinfunction "PD5_(XCK_AIN4/PCINT12)_11") (pintype "bidirectional"))
    )
    (net (code "41") (name "Net-(D5-A)") (class "Default")
      (node (ref "D5") (pin "2") (pinfunction "A_2") (pintype "passive"))
      (node (ref "R5B") (pin "2") (pinfunction "2_2") (pintype "passive"))
    )
    (net (code "42") (name "Net-(D5-C)") (class "Default")
      (node (ref "D5") (pin "1") (pinfunction "C_1") (pintype "passive"))
      (node (ref "U2") (pin "10") (pinfunction "PD4_(INT5/AIN3)_10") (pintype "bidirectional"))
    )
    (net (code "43") (name "Net-(F1-Pad1)") (class "Default")
      (node (ref "F1") (pin "1") (pinfunction "1_1") (pintype "passive"))
      (node (ref "J3") (pin "1") (pinfunction "1_1") (pintype "passive"))
    )
    (net (code "44") (name "Net-(J3-Pad2)") (class "Default")
      (node (ref "J3") (pin "2") (pinfunction "2_2") (pintype "passive"))
      (node (ref "R3D") (pin "2") (pinfunction "2_2") (pintype "passive"))
      (node (ref "Z2") (pin "1") (pinfunction "1_1") (pintype "passive"))
    )
    (net (code "45") (name "Net-(J3-Pad3)") (class "Default")
      (node (ref "J3") (pin "3") (pinfunction "3_3") (pintype "passive"))
      (node (ref "R3A") (pin "1") (pinfunction "1_1") (pintype "passive"))
      (node (ref "Z1") (pin "1") (pinfunction "1_1") (pintype "passive"))
    )
    (net (code "46") (name "Net-(U2-(PC0)_XTAL2)") (class "Default")
      (node (ref "C5") (pin "2") (pinfunction "2_2") (pintype "passive"))
      (node (ref "R1") (pin "1") (pinfunction "1_1") (pintype "passive"))
      (node (ref "U2") (pin "2") (pinfunction "(PC0)_XTAL2_2") (pintype "bidirectional"))
      (node (ref "Y1") (pin "1") (pinfunction "1_1") (pintype "passive"))
    )
    (net (code "47") (name "Net-(U2-D+)") (class "Default")
      (node (ref "R3A") (pin "2") (pinfunction "2_2") (pintype "passive"))
      (node (ref "U2") (pin "29") (pinfunction "D+_29") (pintype "bidirectional"))
    )
    (net (code "48") (name "Net-(U2-D-)") (class "Default")
      (node (ref "R3D") (pin "1") (pinfunction "1_1") (pintype "passive"))
      (node (ref "U2") (pin "30") (pinfunction "D-_30") (pintype "bidirectional"))
    )
    (net (code "49") (name "Net-(U2-PD2_(RXD1{slash}AIN1{slash}INT2))") (class "Default")
      (node (ref "R4A") (pin "2") (pinfunction "2_2") (pintype "passive"))
      (node (ref "U2") (pin "8") (pinfunction "PD2_(RXD1/AIN1/INT2)_8") (pintype "bidirectional"))
    )
    (net (code "50") (name "Net-(U2-PD3_(TXD1{slash}INT3))") (class "Default")
      (node (ref "R4B") (pin "2") (pinfunction "2_2") (pintype "passive"))
      (node (ref "U2") (pin "9") (pinfunction "PD3_(TXD1/INT3)_9") (pintype "bidirectional"))
    )
    (net (code "51") (name "Net-(U2-PD7_(~{CTS}{slash}~{HWB}{slash}AIN6{slash}T0{slash}INT7))") (class "Default")
      (node (ref "C11") (pin "2") (pinfunction "2_2") (pintype "passive"))
      (node (ref "R5D") (pin "2") (pinfunction "2_2") (pintype "passive"))
      (node (ref "U2") (pin "13") (pinfunction "PD7_(~{CTS}/~{HWB}/AIN6/T0/INT7)_13") (pintype "bidirectional"))
    )
    (net (code "52") (name "Net-(U2-UCAP)") (class "Default")
      (node (ref "C8") (pin "2") (pinfunction "2_2") (pintype "passive"))
      (node (ref "U2") (pin "27") (pinfunction "UCAP_27") (pintype "power_in"))
    )
    (net (code "53") (name "Net-(U2-UGND)") (class "Default")
      (node (ref "C8") (pin "1") (pinfunction "1_1") (pintype "passive"))
      (node (ref "J10") (pin "2") (pinfunction "2_2") (pintype "passive"))
      (node (ref "J3") (pin "4") (pinfunction "4_4") (pintype "passive"))
      (node (ref "L1") (pin "2") (pinfunction "2_2") (pintype "passive"))
      (node (ref "U2") (pin "28") (pinfunction "UGND_28") (pintype "power_in"))
    )
    (net (code "54") (name "Net-(U2-XTAL1)") (class "Default")
      (node (ref "C4") (pin "2") (pinfunction "2_2") (pintype "passive"))
      (node (ref "R1") (pin "2") (pinfunction "2_2") (pintype "passive"))
      (node (ref "U2") (pin "1") (pinfunction "XTAL1_1") (pintype "input"))
      (node (ref "Y1") (pin "2") (pinfunction "2_2") (pintype "passive"))
    )
    (net (code "55") (name "Net-(ZU1-VCC)") (class "Default")
      (node (ref "C7") (pin "1") (pinfunction "1_1") (pintype "passive"))
      (node (ref "L2") (pin "2") (pinfunction "2_2") (pintype "passive"))
      (node (ref "ZU1") (pin "7") (pinfunction "VCC_7") (pintype "power_in"))
    )
    (net (code "56") (name "TP_3V3") (class "Default")
      (node (ref "C6") (pin "1") (pinfunction "1_1") (pintype "passive"))
      (node (ref "U4") (pin "5") (pinfunction "VOUT_5") (pintype "power_in"))
    )
    (net (code "57") (name "TP_CMP") (class "Default")
      (node (ref "RN1") (pin "1") (pinfunction "1_1") (pintype "passive"))
      (node (ref "RN2") (pin "2") (pinfunction "2_2") (pintype "passive"))
      (node (ref "U3") (pin "3") (pinfunction "1IN+_3") (pintype "input"))
    )
    (net (code "58") (name "TP_GATE") (class "Default")
      (node (ref "Q1") (pin "1") (pinfunction "G_1") (pintype "passive"))
      (node (ref "U3") (pin "1") (pinfunction "1OUT_1") (pintype "output"))
    )
    (net (code "59") (name "TP_XT1") (class "Default")
      (node (ref "R2") (pin "2") (pinfunction "2_2") (pintype "passive"))
      (node (ref "U5") (pin "1") (pinfunction "C1_1") (pintype "passive"))
      (node (ref "ZU1") (pin "9") (pinfunction "PB6_(PCINT6/XTAL1/TOSC1)_9") (pintype "bidirectional"))
    )
    (net (code "60") (name "TP_XT2") (class "Default")
      (node (ref "R2") (pin "1") (pinfunction "1_1") (pintype "passive"))
      (node (ref "U5") (pin "3") (pinfunction "C2_3") (pintype "passive"))
      (node (ref "ZU1") (pin "10") (pinfunction "PB7_(PCINT7/XTAL2/TOSC2)_10") (pintype "bidirectional"))
    )
    (net (code "61") (name "VIN") (class "Default")
      (node (ref "C1") (pin "2") (pinfunction "A_2") (pintype "passive"))
      (node (ref "D1") (pin "1") (pinfunction "K_1") (pintype "passive"))
      (node (ref "J6") (pin "8") (pinfunction "8_8") (pintype "passive"))
      (node (ref "RN1") (pin "2") (pinfunction "2_2") (pintype "passive"))
      (node (ref "U1") (pin "3") (pinfunction "INPUT_3") (pintype "power_in"))
    )
    (net (code "62") (name "unconnected-(J2-MNT_1-Pad9)") (class "Default")
      (node (ref "J2") (pin "9") (pinfunction "MNT_1_9") (pintype "passive+no_connect"))
    )
    (net (code "63") (name "unconnected-(J2-MNT_2-Pad10)") (class "Default")
      (node (ref "J2") (pin "10") (pinfunction "MNT_2_10") (pintype "passive+no_connect"))
    )
    (net (code "64") (name "unconnected-(J4-MNT_1-Pad7)") (class "Default")
      (node (ref "J4") (pin "7") (pinfunction "MNT_1_7") (pintype "passive+no_connect"))
    )
    (net (code "65") (name "unconnected-(J4-MNT_2-Pad8)") (class "Default")
      (node (ref "J4") (pin "8") (pinfunction "MNT_2_8") (pintype "passive+no_connect"))
    )
    (net (code "66") (name "unconnected-(J5-MNT_1-Pad11)") (class "Default")
      (node (ref "J5") (pin "11") (pinfunction "MNT_1_11") (pintype "passive"))
    )
    (net (code "67") (name "unconnected-(J5-MNT_2-Pad12)") (class "Default")
      (node (ref "J5") (pin "12") (pinfunction "MNT_2_12") (pintype "passive"))
    )
    (net (code "68") (name "unconnected-(J6-MNT_1-Pad9)") (class "Default")
      (node (ref "J6") (pin "9") (pinfunction "MNT_1_9") (pintype "passive+no_connect"))
    )
    (net (code "69") (name "unconnected-(J6-MNT_2-Pad10)") (class "Default")
      (node (ref "J6") (pin "10") (pinfunction "MNT_2_10") (pintype "passive+no_connect"))
    )
    (net (code "70") (name "unconnected-(J6-Pad1)") (class "Default")
      (node (ref "J6") (pin "1") (pinfunction "1_1") (pintype "passive"))
    )
    (net (code "71") (name "unconnected-(R3B-Pad1)") (class "Default")
      (node (ref "R3B") (pin "1") (pinfunction "1_1") (pintype "passive+no_connect"))
    )
    (net (code "72") (name "unconnected-(R3B-Pad2)") (class "Default")
      (node (ref "R3B") (pin "2") (pinfunction "2_2") (pintype "passive+no_connect"))
    )
    (net (code "73") (name "unconnected-(R3C-Pad1)") (class "Default")
      (node (ref "R3C") (pin "1") (pinfunction "1_1") (pintype "passive+no_connect"))
    )
    (net (code "74") (name "unconnected-(R3C-Pad2)") (class "Default")
      (node (ref "R3C") (pin "2") (pinfunction "2_2") (pintype "passive+no_connect"))
    )
    (net (code "75") (name "unconnected-(U2-PB0_(~{SS}{slash}PCINT0)-Pad14)") (class "Default")
      (node (ref "U2") (pin "14") (pinfunction "PB0_(~{SS}/PCINT0)_14") (pintype "bidirectional+no_connect"))
    )
    (net (code "76") (name "unconnected-(U2-PC2_(PCINT11{slash}AIN2)-Pad5)") (class "Default")
      (node (ref "U2") (pin "5") (pinfunction "PC2_(PCINT11/AIN2)_5") (pintype "bidirectional+no_connect"))
    )
    (net (code "77") (name "unconnected-(U2-PC4_(PCINT10)-Pad26)") (class "Default")
      (node (ref "U2") (pin "26") (pinfunction "PC4_(PCINT10)_26") (pintype "bidirectional+no_connect"))
    )
    (net (code "78") (name "unconnected-(U2-PC5_(PCINT9{slash}OC.1B)-Pad25)") (class "Default")
      (node (ref "U2") (pin "25") (pinfunction "PC5_(PCINT9/OC.1B)_25") (pintype "bidirectional+no_connect"))
    )
    (net (code "79") (name "unconnected-(U2-PC6_(OC.1A{slash}PCINT8)-Pad23)") (class "Default")
      (node (ref "U2") (pin "23") (pinfunction "PC6_(OC.1A/PCINT8)_23") (pintype "bidirectional+no_connect"))
    )
    (net (code "80") (name "unconnected-(U2-PC7_(INT4{slash}ICP1{slash}CLKO)-Pad22)") (class "Default")
      (node (ref "U2") (pin "22") (pinfunction "PC7_(INT4/ICP1/CLKO)_22") (pintype "bidirectional+no_connect"))
    )
    (net (code "81") (name "unconnected-(U2-PD0_(OC.0B{slash}INT0)-Pad6)") (class "Default")
      (node (ref "U2") (pin "6") (pinfunction "PD0_(OC.0B/INT0)_6") (pintype "bidirectional+no_connect"))
    )
    (net (code "82") (name "unconnected-(U2-PD1_(AIN0{slash}INT1)-Pad7)") (class "Default")
      (node (ref "U2") (pin "7") (pinfunction "PD1_(AIN0/INT1)_7") (pintype "bidirectional+no_connect"))
    )
    (net (code "83") (name "unconnected-(U2-PD6_(~{RTS}{slash}AIN5{slash}INT6)-Pad12)") (class "Default")
      (node (ref "U2") (pin "12") (pinfunction "PD6_(~{RTS}/AIN5/INT6)_12") (pintype "bidirectional+no_connect"))
    )
    (net (code "84") (name "unconnected-(U3A-GND-Pad4)") (class "Default")
      (node (ref "U3") (pin "4") (pinfunction "GND_4") (pintype "power_in+no_connect"))
    )
    (net (code "85") (name "unconnected-(U3A-VCC+-Pad8)") (class "Default")
      (node (ref "U3") (pin "8") (pinfunction "VCC+_8") (pintype "power_in+no_connect"))
    )
    (net (code "86") (name "unconnected-(U4-BYPASS-Pad4)") (class "Default")
      (node (ref "U4") (pin "4") (pinfunction "BYPASS_4") (pintype "passive+no_connect"))
    )
    (net (code "87") (name "unconnected-(U4-GND-Pad2)") (class "Default")
      (node (ref "U4") (pin "2") (pinfunction "GND_2") (pintype "power_in"))
    )
    (net (code "88") (name "unconnected-(U5-GND-Pad2)") (class "Default")
      (node (ref "U5") (pin "2") (pinfunction "GND_2") (pintype "power_in"))
    )
  )
)
